# Wallboxsteuerung22042021.net
KiCad netlist of a schematic drawn in EAGLE
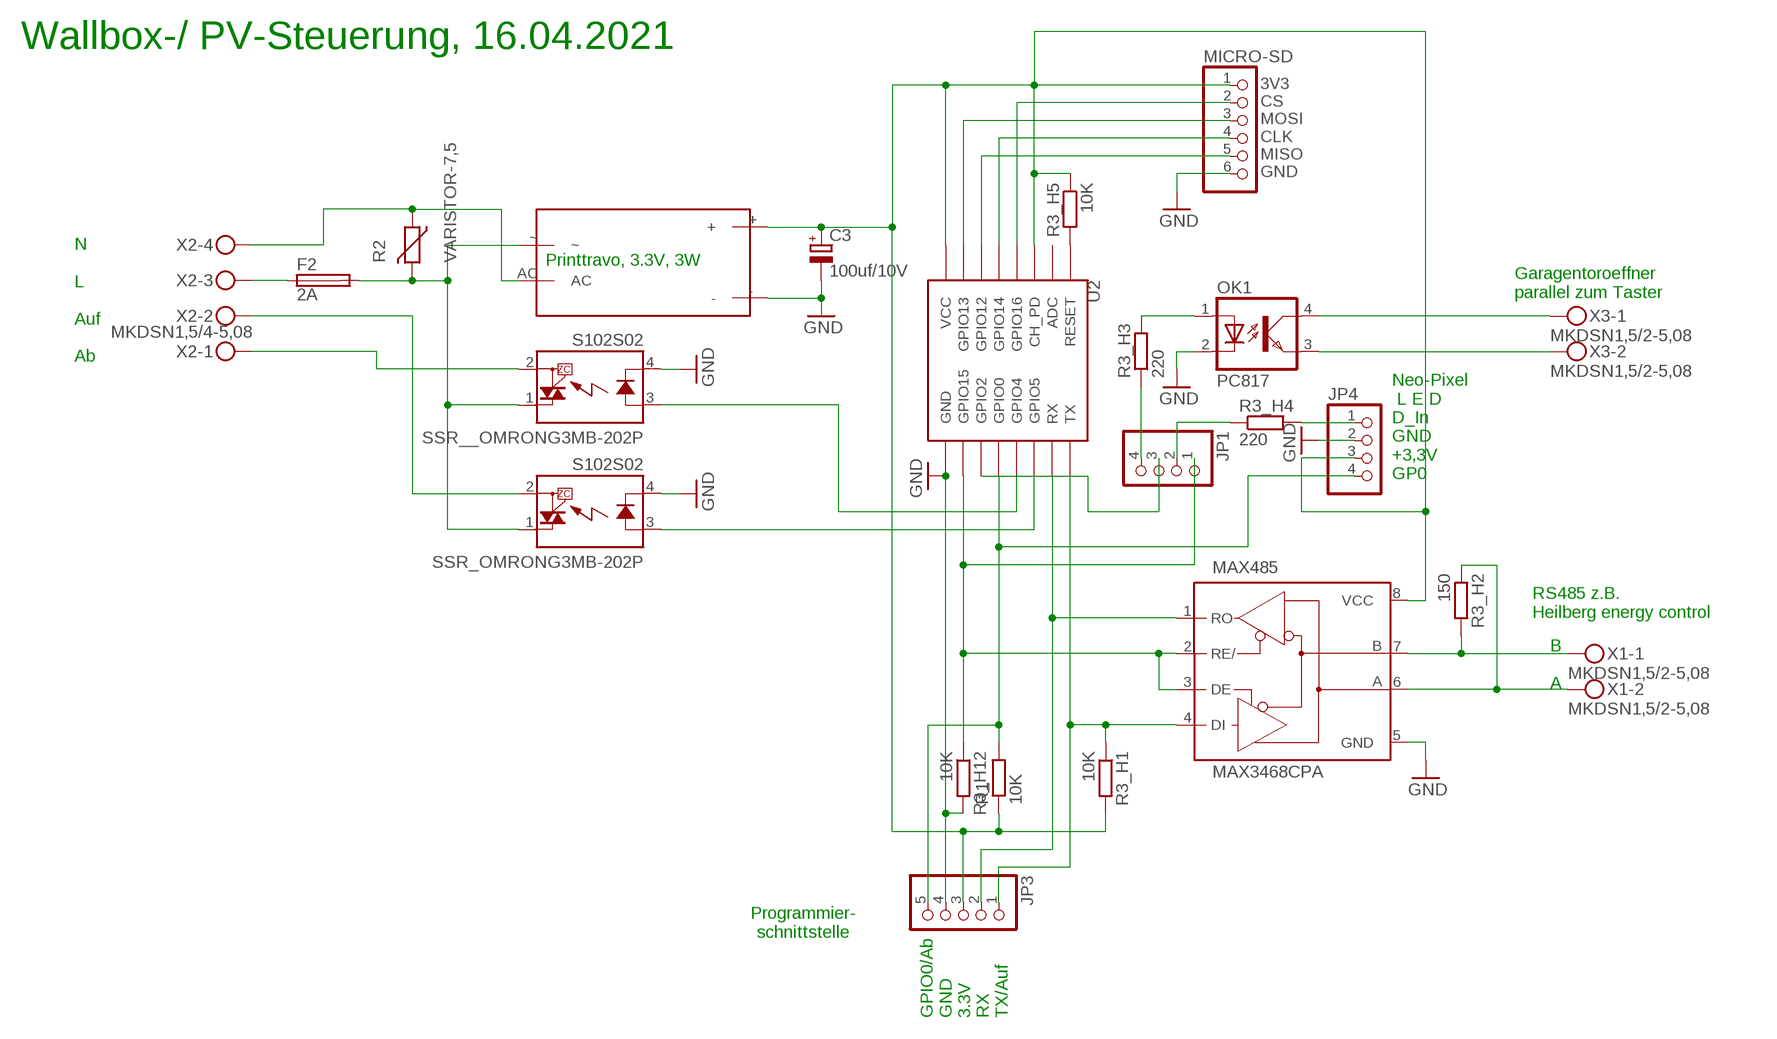
[diagram p0: schematic, sheet 1]

(export (version "E")
  (design (tool "Eeschema 10.0.6"))
  (components
    (comp (ref "C3")
      (value "100uf/10V")
      (footprint "eagle-import:E2,5-7")
      (libsource (lib "eagle-import") (part "CPOL-EUE2.5-7"))
    )
    (comp (ref "F2")
      (value "2A")
      (footprint "eagle-import:LITTLEFUSE")
      (libsource (lib "eagle-import") (part "LITTLEFUSE"))
    )
    (comp (ref "JP1")
      (value "PINHD-1X4")
      (footprint "eagle-import:1X04")
      (libsource (lib "eagle-import") (part "PINHD-1X4"))
    )
    (comp (ref "JP3")
      (value "PINHD-1X5")
      (footprint "eagle-import:1X05")
      (libsource (lib "eagle-import") (part "PINHD-1X5"))
    )
    (comp (ref "JP4")
      (value "PINHD-1X4")
      (footprint "eagle-import:1X04")
      (libsource (lib "eagle-import") (part "PINHD-1X4"))
    )
    (comp (ref "MAX485")
      (value "MAX3468CPA")
      (footprint "eagle-import:DIL08")
      (libsource (lib "eagle-import") (part "MAX34PA68C"))
    )
    (comp (ref "MICRO-SD")
      (value "PINHD-1X6")
      (footprint "eagle-import:1X06")
      (libsource (lib "eagle-import") (part "PINHD-1X6"))
    )
    (comp (ref "OK1")
      (value "PC817")
      (footprint "eagle-import:DIL04")
      (fields (field (name "MPN") "PC817X4J000F"))
      (libsource (lib "eagle-import") (part "PC817"))
    )
    (comp (ref "PRINTTRAFO3.3V,_3W")
      (value "PRINTTRAFO")
      (footprint "eagle-import:PRINTTRAFO")
      (libsource (lib "eagle-import") (part "PRINTTRAFO"))
    )
    (comp (ref "R1")
      (value "10K")
      (footprint "eagle-import:0207_7")
      (libsource (lib "eagle-import") (part "R-EU_0207/7"))
    )
    (comp (ref "R2")
      (value "VARISTOR-7,5")
      (footprint "eagle-import:R-7,5")
      (libsource (lib "eagle-import") (part "VARISTOR-7,5"))
    )
    (comp (ref "R3_H1")
      (value "10K")
      (footprint "eagle-import:0309V")
      (libsource (lib "eagle-import") (part "R-EU_0309/V"))
    )
    (comp (ref "R3_H2")
      (value "150")
      (footprint "eagle-import:0309V")
      (libsource (lib "eagle-import") (part "R-EU_0309/V"))
    )
    (comp (ref "R3_H3")
      (value "220")
      (footprint "eagle-import:0309V")
      (libsource (lib "eagle-import") (part "R-EU_0309/V"))
    )
    (comp (ref "R3_H4")
      (value "220")
      (footprint "eagle-import:0309V")
      (libsource (lib "eagle-import") (part "R-EU_0309/V"))
    )
    (comp (ref "R3_H5")
      (value "10K")
      (footprint "eagle-import:0309V")
      (libsource (lib "eagle-import") (part "R-EU_0309/V"))
    )
    (comp (ref "R3_H12")
      (value "10K")
      (footprint "eagle-import:0207_2V")
      (libsource (lib "eagle-import") (part "R-EU_0207/2V"))
    )
    (comp (ref "SSR_OMRONG3MB-202P")
      (value "S102S02")
      (footprint "eagle-import:S202S02")
      (libsource (lib "eagle-import") (part "S02S021"))
    )
    (comp (ref "SSR__OMRONG3MB-202P")
      (value "S102S02")
      (footprint "eagle-import:S202S02")
      (libsource (lib "eagle-import") (part "S02S021"))
    )
    (comp (ref "U2")
      (value "ESP12SMD")
      (footprint "eagle-import:ESP12-SMD")
      (libsource (lib "eagle-import") (part "ESP12SMD"))
    )
    (comp (ref "X1")
      (value "MKDSN1,5/2-5,08")
      (footprint "eagle-import:MKDSN1,5_2-5,08")
      (libsource (lib "eagle-import") (part "MKDSN1,5/2-5,08"))
    )
    (comp (ref "X2")
      (value "MKDSN1,5/4-5,08")
      (footprint "eagle-import:MKDSN1,5_4-5,08")
      (libsource (lib "eagle-import") (part "MKDSN1,5/4-5,08"))
    )
    (comp (ref "X3")
      (value "MKDSN1,5/2-5,08")
      (footprint "eagle-import:MKDSN1,5_2-5,08")
      (libsource (lib "eagle-import") (part "MKDSN1,5/2-5,08"))
    )
  )
  (nets
    (net (code "1") (name "GND") (class "Default")
      (node (ref "C3") (pin "-") (pinfunction "-_-") (pintype "passive"))
      (node (ref "JP3") (pin "4") (pinfunction "4_4") (pintype "passive"))
      (node (ref "JP4") (pin "2") (pinfunction "2_2") (pintype "passive"))
      (node (ref "MAX485") (pin "5") (pinfunction "GND_5") (pintype "power_in"))
      (node (ref "MICRO-SD") (pin "6") (pinfunction "6_6") (pintype "passive"))
      (node (ref "OK1") (pin "2") (pinfunction "C_2") (pintype "passive"))
      (node (ref "PRINTTRAFO3.3V,_3W") (pin "-") (pinfunction "-_-") (pintype "bidirectional"))
      (node (ref "R3_H12") (pin "2") (pinfunction "2_2") (pintype "passive"))
      (node (ref "SSR_OMRONG3MB-202P") (pin "4") (pinfunction "K_4") (pintype "passive"))
      (node (ref "SSR__OMRONG3MB-202P") (pin "4") (pinfunction "K_4") (pintype "passive"))
      (node (ref "U2") (pin "GND") (pinfunction "GND_GND") (pintype "bidirectional"))
    )
    (net (code "2") (name "Net-(JP1-Pad2)") (class "Default")
      (node (ref "JP1") (pin "2") (pinfunction "2_2") (pintype "passive"))
      (node (ref "R3_H4") (pin "1") (pinfunction "1_1") (pintype "passive"))
    )
    (net (code "3") (name "Net-(JP1-Pad3)") (class "Default")
      (node (ref "JP1") (pin "3") (pinfunction "3_3") (pintype "passive"))
      (node (ref "U2") (pin "GPIO2") (pinfunction "GPIO2_GPIO2") (pintype "bidirectional"))
    )
    (net (code "4") (name "Net-(JP1-Pad4)") (class "Default")
      (node (ref "JP1") (pin "4") (pinfunction "4_4") (pintype "passive"))
      (node (ref "R3_H3") (pin "1") (pinfunction "1_1") (pintype "passive"))
    )
    (net (code "5") (name "Net-(JP3-Pad5)") (class "Default")
      (node (ref "JP3") (pin "5") (pinfunction "5_5") (pintype "passive"))
      (node (ref "JP4") (pin "4") (pinfunction "4_4") (pintype "passive"))
      (node (ref "R1") (pin "2") (pinfunction "2_2") (pintype "passive"))
      (node (ref "U2") (pin "GPIO0") (pinfunction "GPIO0_GPIO0") (pintype "bidirectional"))
    )
    (net (code "6") (name "Net-(JP4-Pad1)") (class "Default")
      (node (ref "JP4") (pin "1") (pinfunction "1_1") (pintype "passive"))
      (node (ref "R3_H4") (pin "2") (pinfunction "2_2") (pintype "passive"))
    )
    (net (code "7") (name "Net-(MAX485-A)") (class "Default")
      (node (ref "MAX485") (pin "6") (pinfunction "A_6") (pintype "passive"))
      (node (ref "R3_H2") (pin "1") (pinfunction "1_1") (pintype "passive"))
      (node (ref "X1") (pin "2") (pinfunction "KL_2") (pintype "passive"))
    )
    (net (code "8") (name "Net-(MAX485-B)") (class "Default")
      (node (ref "MAX485") (pin "7") (pinfunction "B_7") (pintype "passive"))
      (node (ref "R3_H2") (pin "2") (pinfunction "2_2") (pintype "passive"))
      (node (ref "X1") (pin "1") (pinfunction "KL_1") (pintype "passive"))
    )
    (net (code "9") (name "Net-(MAX485-DE)") (class "Default")
      (node (ref "JP1") (pin "1") (pinfunction "1_1") (pintype "passive"))
      (node (ref "MAX485") (pin "2") (pinfunction "RE/_2") (pintype "input"))
      (node (ref "MAX485") (pin "3") (pinfunction "DE_3") (pintype "input"))
      (node (ref "R3_H12") (pin "1") (pinfunction "1_1") (pintype "passive"))
      (node (ref "U2") (pin "GPIO15") (pinfunction "GPIO15_GPIO15") (pintype "bidirectional"))
    )
    (net (code "10") (name "Net-(MAX485-DI)") (class "Default")
      (node (ref "JP3") (pin "1") (pinfunction "1_1") (pintype "passive"))
      (node (ref "MAX485") (pin "4") (pinfunction "DI_4") (pintype "input"))
      (node (ref "R3_H1") (pin "1") (pinfunction "1_1") (pintype "passive"))
      (node (ref "U2") (pin "TXD0") (pinfunction "TX_TXD0") (pintype "bidirectional"))
    )
    (net (code "11") (name "Net-(MAX485-RO)") (class "Default")
      (node (ref "JP3") (pin "2") (pinfunction "2_2") (pintype "passive"))
      (node (ref "MAX485") (pin "1") (pinfunction "RO_1") (pintype "output"))
      (node (ref "U2") (pin "RXD0") (pinfunction "RX_RXD0") (pintype "bidirectional"))
    )
    (net (code "12") (name "Net-(MAX485-VCC)") (class "Default")
      (node (ref "C3") (pin "+") (pinfunction "+_+") (pintype "passive"))
      (node (ref "JP3") (pin "3") (pinfunction "3_3") (pintype "passive"))
      (node (ref "JP4") (pin "3") (pinfunction "3_3") (pintype "passive"))
      (node (ref "MAX485") (pin "8") (pinfunction "VCC_8") (pintype "power_in"))
      (node (ref "MICRO-SD") (pin "1") (pinfunction "1_1") (pintype "passive"))
      (node (ref "PRINTTRAFO3.3V,_3W") (pin "+") (pinfunction "+_+") (pintype "bidirectional"))
      (node (ref "R1") (pin "1") (pinfunction "1_1") (pintype "passive"))
      (node (ref "R3_H1") (pin "2") (pinfunction "2_2") (pintype "passive"))
      (node (ref "R3_H5") (pin "1") (pinfunction "1_1") (pintype "passive"))
      (node (ref "U2") (pin "CH_PD") (pinfunction "CH_PD_CH_PD") (pintype "bidirectional"))
      (node (ref "U2") (pin "VCC") (pinfunction "VCC_VCC") (pintype "bidirectional"))
    )
    (net (code "13") (name "Net-(MICRO-SD-Pad2)") (class "Default")
      (node (ref "MICRO-SD") (pin "2") (pinfunction "2_2") (pintype "passive"))
      (node (ref "U2") (pin "GPIO16") (pinfunction "GPIO16_GPIO16") (pintype "bidirectional"))
    )
    (net (code "14") (name "Net-(MICRO-SD-Pad3)") (class "Default")
      (node (ref "MICRO-SD") (pin "3") (pinfunction "3_3") (pintype "passive"))
      (node (ref "U2") (pin "GPIO13") (pinfunction "GPIO13_GPIO13") (pintype "bidirectional"))
    )
    (net (code "15") (name "Net-(MICRO-SD-Pad4)") (class "Default")
      (node (ref "MICRO-SD") (pin "4") (pinfunction "4_4") (pintype "passive"))
      (node (ref "U2") (pin "GPIO14") (pinfunction "GPIO14_GPIO14") (pintype "bidirectional"))
    )
    (net (code "16") (name "Net-(MICRO-SD-Pad5)") (class "Default")
      (node (ref "MICRO-SD") (pin "5") (pinfunction "5_5") (pintype "passive"))
      (node (ref "U2") (pin "GPIO12") (pinfunction "GPIO12_GPIO12") (pintype "bidirectional"))
    )
    (net (code "17") (name "Net-(OK1-A)") (class "Default")
      (node (ref "OK1") (pin "1") (pinfunction "A_1") (pintype "passive"))
      (node (ref "R3_H3") (pin "2") (pinfunction "2_2") (pintype "passive"))
    )
    (net (code "18") (name "Net-(OK1-COL)") (class "Default")
      (node (ref "OK1") (pin "4") (pinfunction "COL_4") (pintype "passive"))
      (node (ref "X3") (pin "1") (pinfunction "KL_1") (pintype "passive"))
    )
    (net (code "19") (name "Net-(OK1-EMIT)") (class "Default")
      (node (ref "OK1") (pin "3") (pinfunction "EMIT_3") (pintype "passive"))
      (node (ref "X3") (pin "2") (pinfunction "KL_2") (pintype "passive"))
    )
    (net (code "20") (name "Net-(R3_H5-Pad2)") (class "Default")
      (node (ref "R3_H5") (pin "2") (pinfunction "2_2") (pintype "passive"))
      (node (ref "U2") (pin "RESET") (pinfunction "RESET_RESET") (pintype "bidirectional"))
    )
    (net (code "21") (name "Net-(SSR_OMRONG3MB-202P-A)") (class "Default")
      (node (ref "SSR_OMRONG3MB-202P") (pin "3") (pinfunction "A_3") (pintype "passive"))
      (node (ref "U2") (pin "GPIO4") (pinfunction "GPIO5_GPIO4") (pintype "bidirectional"))
    )
    (net (code "22") (name "Net-(SSR_OMRONG3MB-202P-DS1)") (class "Default")
      (node (ref "F2") (pin "2") (pinfunction "2_2") (pintype "passive"))
      (node (ref "PRINTTRAFO3.3V,_3W") (pin "~") (pinfunction "~_~") (pintype "bidirectional"))
      (node (ref "R2") (pin "2") (pinfunction "2_2") (pintype "passive"))
      (node (ref "SSR_OMRONG3MB-202P") (pin "1") (pinfunction "DS1_1") (pintype "passive"))
      (node (ref "SSR__OMRONG3MB-202P") (pin "1") (pinfunction "DS1_1") (pintype "passive"))
    )
    (net (code "23") (name "Net-(SSR_OMRONG3MB-202P-DS2)") (class "Default")
      (node (ref "SSR_OMRONG3MB-202P") (pin "2") (pinfunction "DS2_2") (pintype "passive"))
      (node (ref "X2") (pin "2") (pinfunction "KL_2") (pintype "passive"))
    )
    (net (code "24") (name "Net-(SSR__OMRONG3MB-202P-A)") (class "Default")
      (node (ref "SSR__OMRONG3MB-202P") (pin "3") (pinfunction "A_3") (pintype "passive"))
      (node (ref "U2") (pin "GPIO5") (pinfunction "GPIO4_GPIO5") (pintype "bidirectional"))
    )
    (net (code "25") (name "Net-(SSR__OMRONG3MB-202P-DS2)") (class "Default")
      (node (ref "SSR__OMRONG3MB-202P") (pin "2") (pinfunction "DS2_2") (pintype "passive"))
      (node (ref "X2") (pin "1") (pinfunction "KL_1") (pintype "passive"))
    )
    (net (code "26") (name "Net-(X2C-KL)") (class "Default")
      (node (ref "F2") (pin "1") (pinfunction "1_1") (pintype "passive"))
      (node (ref "X2") (pin "3") (pinfunction "KL_3") (pintype "passive"))
    )
    (net (code "27") (name "Net-(X2D-KL)") (class "Default")
      (node (ref "PRINTTRAFO3.3V,_3W") (pin "AC") (pinfunction "AC_AC") (pintype "bidirectional"))
      (node (ref "R2") (pin "1") (pinfunction "1_1") (pintype "passive"))
      (node (ref "X2") (pin "4") (pinfunction "KL_4") (pintype "passive"))
    )
    (net (code "28") (name "unconnected-(U2-PadADC)") (class "Default")
      (node (ref "U2") (pin "ADC") (pinfunction "ADC_ADC") (pintype "bidirectional"))
    )
  )
)
